# V4-POJ-STM32F103C8T6.net
KiCad netlist of a schematic drawn in EasyEDA Pro
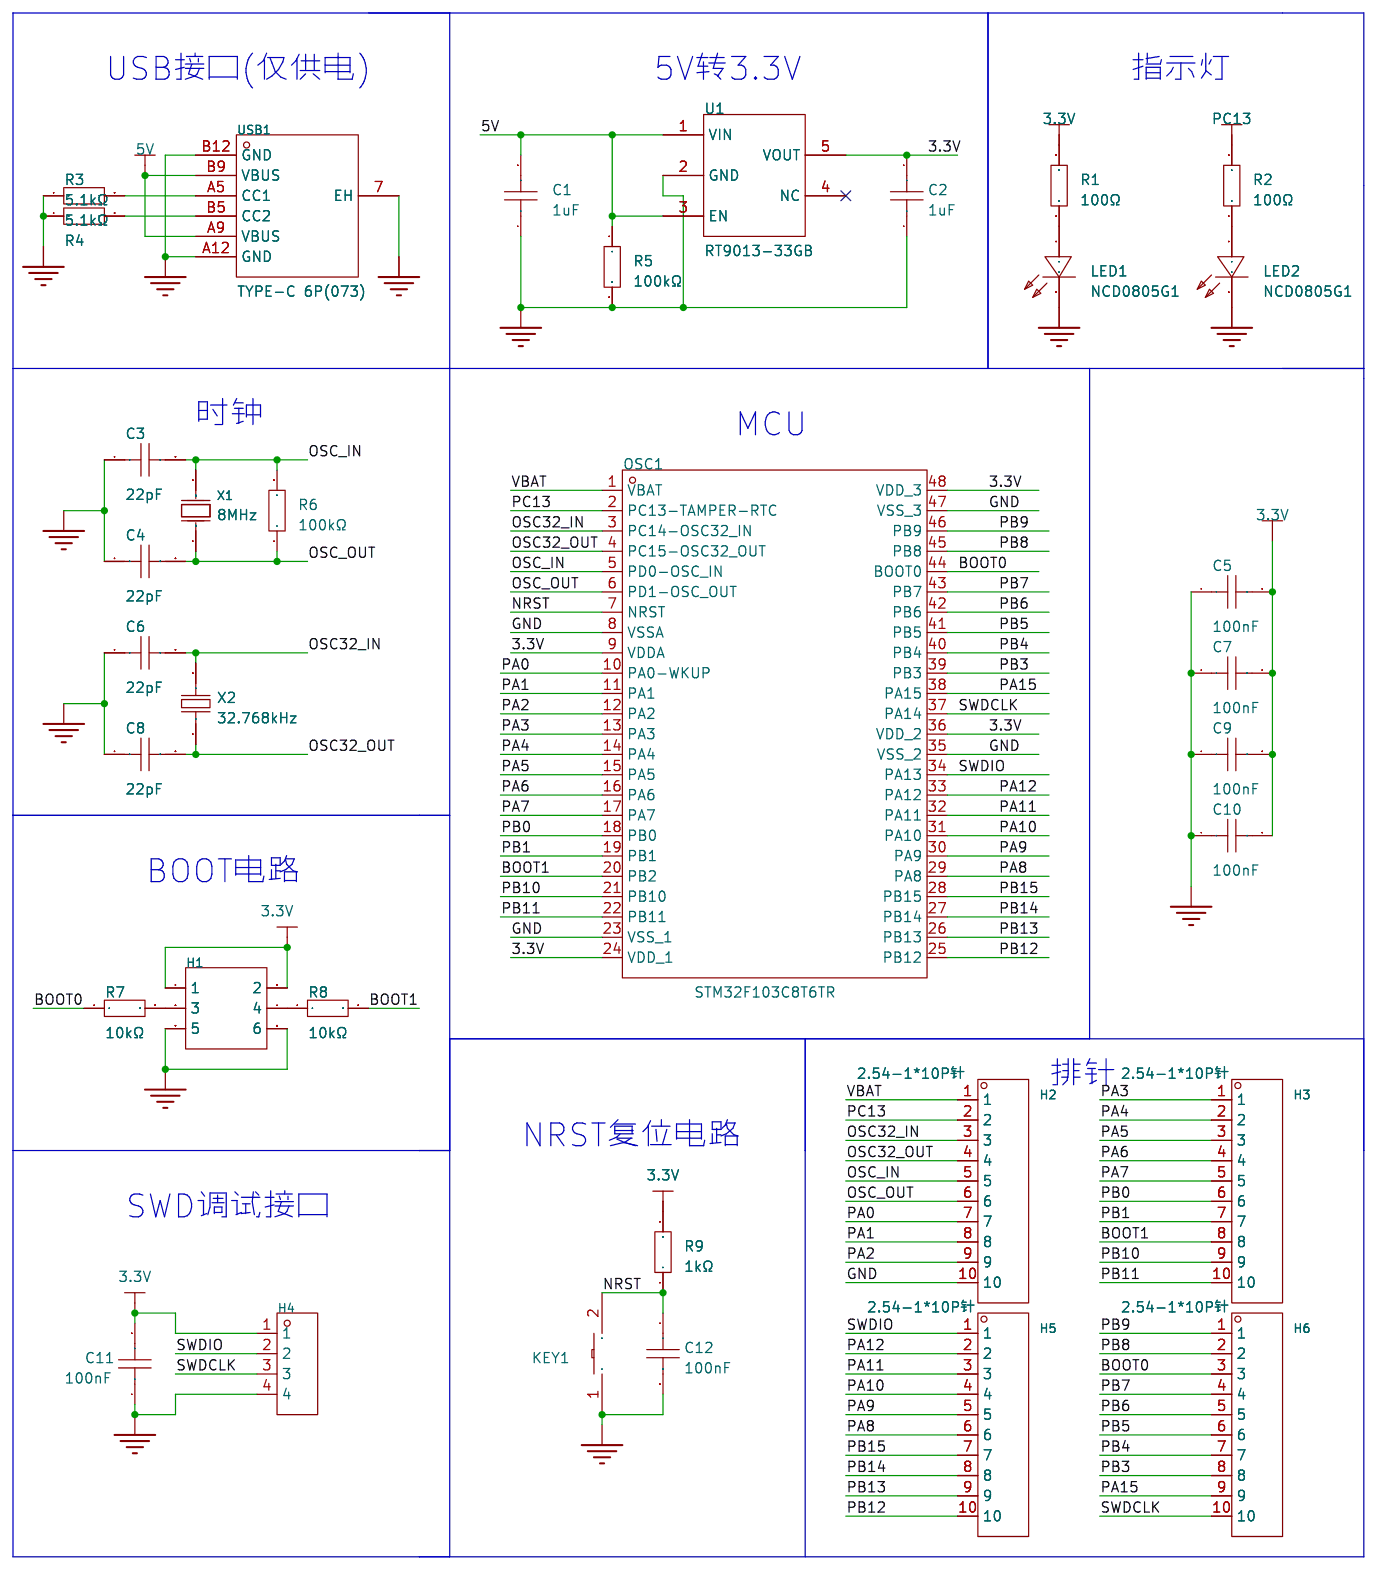
[diagram p0: schematic sheet]

(export (version "E")
  (design (tool "Eeschema 10.0.6"))
  (components
    (comp (ref "C1")
      (value "1uF")
      (footprint "easyedapro:C0603")
      (fields
        (field (name "Manufacturer Part") "CL21B105KBFNNNE")
        (field (name "Manufacturer") "SAMSUNG(三星)")
      )
      (libsource (lib "easyedapro") (part "CapAcitance"))
    )
    (comp (ref "C2")
      (value "1uF")
      (footprint "easyedapro:C0603")
      (fields
        (field (name "Manufacturer Part") "CL21B105KBFNNNE")
        (field (name "Manufacturer") "SAMSUNG(三星)")
      )
      (libsource (lib "easyedapro") (part "CapAcitance"))
    )
    (comp (ref "C3")
      (value "22pF")
      (footprint "easyedapro:C0805")
      (description "容值:22pF;精度:±5%;额定电压:50V;材质(温度系数):C0G;")
      (fields (field (name "Manufacturer Part") "0805CG220J500NT") (field (name "Manufacturer") "FH(风华)"))
      (libsource (lib "easyedapro") (part "0805CG220J500NT_C24658"))
    )
    (comp (ref "C4")
      (value "22pF")
      (footprint "easyedapro:C0805")
      (description "容值:22pF;精度:±5%;额定电压:50V;材质(温度系数):C0G;")
      (fields (field (name "Manufacturer Part") "0805CG220J500NT") (field (name "Manufacturer") "FH(风华)"))
      (libsource (lib "easyedapro") (part "0805CG220J500NT_C24658"))
    )
    (comp (ref "C5")
      (value "100nF")
      (footprint "easyedapro:C0603")
      (fields (field (name "Manufacturer Part") "0805B104K500NT") (field (name "Manufacturer") "FH(风华)"))
      (libsource (lib "easyedapro") (part "CapAcitance"))
    )
    (comp (ref "C6")
      (value "22pF")
      (footprint "easyedapro:C0805")
      (description "容值:22pF;精度:±5%;额定电压:50V;材质(温度系数):C0G;")
      (fields (field (name "Manufacturer Part") "0805CG220J500NT") (field (name "Manufacturer") "FH(风华)"))
      (libsource (lib "easyedapro") (part "0805CG220J500NT_C24658"))
    )
    (comp (ref "C7")
      (value "100nF")
      (footprint "easyedapro:C0603")
      (fields (field (name "Manufacturer Part") "0805B104K500NT") (field (name "Manufacturer") "FH(风华)"))
      (libsource (lib "easyedapro") (part "CapAcitance"))
    )
    (comp (ref "C8")
      (value "22pF")
      (footprint "easyedapro:C0805")
      (description "容值:22pF;精度:±5%;额定电压:50V;材质(温度系数):C0G;")
      (fields (field (name "Manufacturer Part") "0805CG220J500NT") (field (name "Manufacturer") "FH(风华)"))
      (libsource (lib "easyedapro") (part "0805CG220J500NT_C24658"))
    )
    (comp (ref "C9")
      (value "100nF")
      (footprint "easyedapro:C0603")
      (fields (field (name "Manufacturer Part") "0805B104K500NT") (field (name "Manufacturer") "FH(风华)"))
      (libsource (lib "easyedapro") (part "CapAcitance"))
    )
    (comp (ref "C10")
      (value "100nF")
      (footprint "easyedapro:C0603")
      (fields (field (name "Manufacturer Part") "0805B104K500NT") (field (name "Manufacturer") "FH(风华)"))
      (libsource (lib "easyedapro") (part "CapAcitance"))
    )
    (comp (ref "C11")
      (value "100nF")
      (footprint "easyedapro:C0603")
      (fields (field (name "Manufacturer Part") "0805B104K500NT") (field (name "Manufacturer") "FH(风华)"))
      (libsource (lib "easyedapro") (part "CapAcitance"))
    )
    (comp (ref "C12")
      (value "100nF")
      (footprint "easyedapro:C0603")
      (fields (field (name "Manufacturer Part") "0805B104K500NT") (field (name "Manufacturer") "FH(风华)"))
      (libsource (lib "easyedapro") (part "CapAcitance"))
    )
    (comp (ref "H1")
      (value "2.54-2*3P针")
      (footprint "easyedapro:HDR-TH_6P-P2.54-V-M-R2-C3-S2.54-1")
      (fields (field (name "Manufacturer") "BOOMELE(博穆精密)"))
      (libsource (lib "easyedapro") (part "Header-Male-2.54_2x3"))
    )
    (comp (ref "H2")
      (value "2.54-1*10P针")
      (footprint "easyedapro:HDR-TH_10P-P2.54-V-M-1")
      (fields (field (name "Manufacturer") "BOOMELE(博穆精密)"))
      (libsource (lib "easyedapro") (part "Header-Male-2.54_1x10"))
    )
    (comp (ref "H3")
      (value "2.54-1*10P针")
      (footprint "easyedapro:HDR-TH_10P-P2.54-V-M-1")
      (fields (field (name "Manufacturer") "BOOMELE(博穆精密)"))
      (libsource (lib "easyedapro") (part "Header-Male-2.54_1x10"))
    )
    (comp (ref "H4")
      (value "PZ254R-11-04P")
      (footprint "easyedapro:HDR-TH_4P-P2.54-V-M")
      (fields (field (name "Manufacturer") "XFCN(兴飞)"))
      (libsource (lib "easyedapro") (part "PZ254V-11-04P_C2691448"))
    )
    (comp (ref "H5")
      (value "2.54-1*10P针")
      (footprint "easyedapro:HDR-TH_10P-P2.54-V-M-1")
      (fields (field (name "Manufacturer") "BOOMELE(博穆精密)"))
      (libsource (lib "easyedapro") (part "Header-Male-2.54_1x10"))
    )
    (comp (ref "H6")
      (value "2.54-1*10P针")
      (footprint "easyedapro:HDR-TH_10P-P2.54-V-M-1")
      (fields (field (name "Manufacturer") "BOOMELE(博穆精密)"))
      (libsource (lib "easyedapro") (part "Header-Male-2.54_1x10"))
    )
    (comp (ref "KEY1")
      (value "TS-1101-C-W")
      (footprint "easyedapro:SW-SMD_L6.0-W3.3-LS8.0")
      (description "触点电流:50mA;额定电压(AC):-;额定电压(DC):12V;额定功率:-;绝缘电阻:-;电路结构:单刀单掷;安装方式:立贴;带灯:无;作用力:260gf;机械寿命:5万次;带支架:否;")
      (fields (field (name "Manufacturer") "XKB Connectivity(中国星坤)"))
      (libsource (lib "easyedapro") (part "TS-1101-C-W"))
    )
    (comp (ref "LED1")
      (value "NCD0805G1")
      (footprint "easyedapro:LED0805-R-RD")
      (description "发光颜色:翠绿;")
      (fields (field (name "Manufacturer") "国星光电"))
      (libsource (lib "easyedapro") (part "FC-2012UGK-520D5"))
    )
    (comp (ref "LED2")
      (value "NCD0805G1")
      (footprint "easyedapro:LED0805-R-RD")
      (description "发光颜色:翠绿;")
      (fields (field (name "Manufacturer") "国星光电"))
      (libsource (lib "easyedapro") (part "FC-2012UGK-520D5"))
    )
    (comp (ref "OSC1")
      (value "STM32F103C8T6TR")
      (footprint "easyedapro:LQFP-48_L7.0-W7.0-P0.50-LS9.0-BL")
      (fields (field (name "Manufacturer") "ST(意法半导体)"))
      (libsource (lib "easyedapro") (part "STM32F103C8T6TR"))
    )
    (comp (ref "R1")
      (value "100Ω")
      (footprint "easyedapro:R0603")
      (fields
        (field (name "Manufacturer Part") "0805W8F1000T5E")
        (field (name "Manufacturer") "UNI-ROYAL(厚声)")
      )
      (libsource (lib "easyedapro") (part "电阻"))
    )
    (comp (ref "R2")
      (value "100Ω")
      (footprint "easyedapro:R0603")
      (fields
        (field (name "Manufacturer Part") "0805W8F1000T5E")
        (field (name "Manufacturer") "UNI-ROYAL(厚声)")
      )
      (libsource (lib "easyedapro") (part "电阻"))
    )
    (comp (ref "R3")
      (value "5.1kΩ")
      (fields
        (field (name "Manufacturer Part") "0805W8F5101T5E")
        (field (name "Manufacturer") "UNI-ROYAL(厚声)")
      )
      (libsource (lib "easyedapro") (part "电阻"))
    )
    (comp (ref "R4")
      (value "5.1kΩ")
      (fields
        (field (name "Manufacturer Part") "0805W8F5101T5E")
        (field (name "Manufacturer") "UNI-ROYAL(厚声)")
      )
      (libsource (lib "easyedapro") (part "电阻"))
    )
    (comp (ref "R5")
      (value "100kΩ")
      (footprint "easyedapro:R0603")
      (description "阻值:100kΩ;精度:±1%;功率:125mW;温度系数:±100ppm/℃;电阻类型:厚膜电阻;")
      (fields
        (field (name "Manufacturer Part") "0805W8F1003T5E")
        (field (name "Manufacturer") "UNI-ROYAL(厚声)")
      )
      (libsource (lib "easyedapro") (part "电阻"))
    )
    (comp (ref "R6")
      (value "100kΩ")
      (footprint "easyedapro:R0805")
      (description "阻值:100kΩ;精度:±1%;功率:125mW;温度系数:±100ppm/℃;电阻类型:厚膜电阻;")
      (fields
        (field (name "Manufacturer Part") "0805W8F1003T5E")
        (field (name "Manufacturer") "UNI-ROYAL(厚声)")
      )
      (libsource (lib "easyedapro") (part "0805W8F1002T5E"))
    )
    (comp (ref "R7")
      (value "10kΩ")
      (footprint "easyedapro:R0603")
      (fields
        (field (name "Manufacturer Part") "0805W8F1002T5E")
        (field (name "Manufacturer") "UNI-ROYAL(厚声)")
      )
      (libsource (lib "easyedapro") (part "电阻"))
    )
    (comp (ref "R8")
      (value "10kΩ")
      (footprint "easyedapro:R0603")
      (fields
        (field (name "Manufacturer Part") "0805W8F1002T5E")
        (field (name "Manufacturer") "UNI-ROYAL(厚声)")
      )
      (libsource (lib "easyedapro") (part "电阻"))
    )
    (comp (ref "R9")
      (value "1kΩ")
      (footprint "easyedapro:R0603")
      (fields
        (field (name "Manufacturer Part") "0805W8F1001T5E")
        (field (name "Manufacturer") "UNI-ROYAL(厚声)")
      )
      (libsource (lib "easyedapro") (part "电阻"))
    )
    (comp (ref "U1")
      (value "RT9013-33GB")
      (footprint "easyedapro:SOT-23-5_L3.0-W1.7-P0.95-LS2.8-BL")
      (description "输出类型:固定;输出极性:正;最大输入电压:5.5V;输出电压:3.3V;输出电流:500mA;电源纹波抑制比(PSRR):50dB@(10kHz);")
      (fields (field (name "Manufacturer") "RICHTEK(立锜)"))
      (libsource (lib "easyedapro") (part "RT9013-33GB"))
    )
    (comp (ref "USB1")
      (value "TYPE-C 6P(073)")
      (footprint "easyedapro:TYPE-C-SMD_TYPE-C-6P")
      (description "连接器类型:Type-C;标准:-;公母:母座;触点数量:6P;端口数量:1;安装方式:卧贴;额定电流 - 电源:5A;工作温度范围:-25°C~+85°C;")
      (fields (field (name "Manufacturer") "SHOU HAN(首韩)"))
      (libsource (lib "easyedapro") (part "TYPE-C 6P(073)"))
    )
    (comp (ref "X1")
      (value "8MHz")
      (footprint "easyedapro:CRYSTAL-SMD_L5.0-W3.2")
      (description "频率:8MHz;负载电容:20pF;频率公差:±10ppm;")
      (fields (field (name "Manufacturer Part") "X50328MSB2GI") (field (name "Manufacturer") "YXC(扬兴晶振)"))
      (libsource (lib "easyedapro") (part "X50328MSB2GI"))
    )
    (comp (ref "X2")
      (value "32.768kHz")
      (footprint "easyedapro:FC-135R_L3.2-W1.5")
      (description "频率:32.768kHz;频率公差:±20ppm;负载电容:12.5pF;")
      (fields (field (name "Manufacturer Part") "Q13FC1350000400") (field (name "Manufacturer") "EPSON(爱普生)"))
      (libsource (lib "easyedapro") (part "Q13FC1350000400"))
    )
  )
  (nets
    (net (code "1") (name "/BOOT0") (class "Default")
      (node (ref "H6") (pin "3") (pinfunction "3_3") (pintype "input"))
      (node (ref "OSC1") (pin "44") (pinfunction "BOOT0_44") (pintype "input"))
      (node (ref "R7") (pin "1") (pinfunction "1_1") (pintype "input"))
    )
    (net (code "2") (name "/BOOT1") (class "Default")
      (node (ref "H3") (pin "8") (pinfunction "8_8") (pintype "input"))
      (node (ref "OSC1") (pin "20") (pinfunction "PB2_20") (pintype "input"))
      (node (ref "R8") (pin "2") (pinfunction "2_2") (pintype "input"))
    )
    (net (code "3") (name "/NRST") (class "Default")
      (node (ref "C12") (pin "1") (pinfunction "1_1") (pintype "input"))
      (node (ref "KEY1") (pin "2") (pinfunction "2_2") (pintype "input"))
      (node (ref "OSC1") (pin "7") (pinfunction "NRST_7") (pintype "input"))
      (node (ref "R9") (pin "1") (pinfunction "1_1") (pintype "input"))
    )
    (net (code "4") (name "/OSC32_IN") (class "Default")
      (node (ref "C6") (pin "2") (pinfunction "2_2") (pintype "input"))
      (node (ref "H2") (pin "3") (pinfunction "3_3") (pintype "input"))
      (node (ref "OSC1") (pin "3") (pinfunction "PC14-OSC32_IN_3") (pintype "input"))
      (node (ref "X2") (pin "2") (pinfunction "2_2") (pintype "input"))
    )
    (net (code "5") (name "/OSC32_OUT") (class "Default")
      (node (ref "C8") (pin "2") (pinfunction "2_2") (pintype "input"))
      (node (ref "H2") (pin "4") (pinfunction "4_4") (pintype "input"))
      (node (ref "OSC1") (pin "4") (pinfunction "PC15-OSC32_OUT_4") (pintype "input"))
      (node (ref "X2") (pin "1") (pinfunction "1_1") (pintype "input"))
    )
    (net (code "6") (name "/OSC_IN") (class "Default")
      (node (ref "C3") (pin "2") (pinfunction "2_2") (pintype "input"))
      (node (ref "H2") (pin "5") (pinfunction "5_5") (pintype "input"))
      (node (ref "OSC1") (pin "5") (pinfunction "PD0-OSC_IN_5") (pintype "input"))
      (node (ref "R6") (pin "2") (pinfunction "2_2") (pintype "input"))
      (node (ref "X1") (pin "2") (pinfunction "OSC2_2") (pintype "input"))
    )
    (net (code "7") (name "/OSC_OUT") (class "Default")
      (node (ref "C4") (pin "2") (pinfunction "2_2") (pintype "input"))
      (node (ref "H2") (pin "6") (pinfunction "6_6") (pintype "input"))
      (node (ref "OSC1") (pin "6") (pinfunction "PD1-OSC_OUT_6") (pintype "input"))
      (node (ref "R6") (pin "1") (pinfunction "1_1") (pintype "input"))
      (node (ref "X1") (pin "1") (pinfunction "OSC1_1") (pintype "input"))
    )
    (net (code "8") (name "/PA0") (class "Default")
      (node (ref "H2") (pin "7") (pinfunction "7_7") (pintype "input"))
      (node (ref "OSC1") (pin "10") (pinfunction "PA0-WKUP_10") (pintype "input"))
    )
    (net (code "9") (name "/PA1") (class "Default")
      (node (ref "H2") (pin "8") (pinfunction "8_8") (pintype "input"))
      (node (ref "OSC1") (pin "11") (pinfunction "PA1_11") (pintype "input"))
    )
    (net (code "10") (name "/PA2") (class "Default")
      (node (ref "H2") (pin "9") (pinfunction "9_9") (pintype "input"))
      (node (ref "OSC1") (pin "12") (pinfunction "PA2_12") (pintype "input"))
    )
    (net (code "11") (name "/PA3") (class "Default")
      (node (ref "H3") (pin "1") (pinfunction "1_1") (pintype "input"))
      (node (ref "OSC1") (pin "13") (pinfunction "PA3_13") (pintype "input"))
    )
    (net (code "12") (name "/PA4") (class "Default")
      (node (ref "H3") (pin "2") (pinfunction "2_2") (pintype "input"))
      (node (ref "OSC1") (pin "14") (pinfunction "PA4_14") (pintype "input"))
    )
    (net (code "13") (name "/PA5") (class "Default")
      (node (ref "H3") (pin "3") (pinfunction "3_3") (pintype "input"))
      (node (ref "OSC1") (pin "15") (pinfunction "PA5_15") (pintype "input"))
    )
    (net (code "14") (name "/PA6") (class "Default")
      (node (ref "H3") (pin "4") (pinfunction "4_4") (pintype "input"))
      (node (ref "OSC1") (pin "16") (pinfunction "PA6_16") (pintype "input"))
    )
    (net (code "15") (name "/PA7") (class "Default")
      (node (ref "H3") (pin "5") (pinfunction "5_5") (pintype "input"))
      (node (ref "OSC1") (pin "17") (pinfunction "PA7_17") (pintype "input"))
    )
    (net (code "16") (name "/PA8") (class "Default")
      (node (ref "H5") (pin "6") (pinfunction "6_6") (pintype "input"))
      (node (ref "OSC1") (pin "29") (pinfunction "PA8_29") (pintype "input"))
    )
    (net (code "17") (name "/PA9") (class "Default")
      (node (ref "H5") (pin "5") (pinfunction "5_5") (pintype "input"))
      (node (ref "OSC1") (pin "30") (pinfunction "PA9_30") (pintype "input"))
    )
    (net (code "18") (name "/PA10") (class "Default")
      (node (ref "H5") (pin "4") (pinfunction "4_4") (pintype "input"))
      (node (ref "OSC1") (pin "31") (pinfunction "PA10_31") (pintype "input"))
    )
    (net (code "19") (name "/PA11") (class "Default")
      (node (ref "H5") (pin "3") (pinfunction "3_3") (pintype "input"))
      (node (ref "OSC1") (pin "32") (pinfunction "PA11_32") (pintype "input"))
    )
    (net (code "20") (name "/PA12") (class "Default")
      (node (ref "H5") (pin "2") (pinfunction "2_2") (pintype "input"))
      (node (ref "OSC1") (pin "33") (pinfunction "PA12_33") (pintype "input"))
    )
    (net (code "21") (name "/PA15") (class "Default")
      (node (ref "H6") (pin "9") (pinfunction "9_9") (pintype "input"))
      (node (ref "OSC1") (pin "38") (pinfunction "PA15_38") (pintype "input"))
    )
    (net (code "22") (name "/PB0") (class "Default")
      (node (ref "H3") (pin "6") (pinfunction "6_6") (pintype "input"))
      (node (ref "OSC1") (pin "18") (pinfunction "PB0_18") (pintype "input"))
    )
    (net (code "23") (name "/PB1") (class "Default")
      (node (ref "H3") (pin "7") (pinfunction "7_7") (pintype "input"))
      (node (ref "OSC1") (pin "19") (pinfunction "PB1_19") (pintype "input"))
    )
    (net (code "24") (name "/PB3") (class "Default")
      (node (ref "H6") (pin "8") (pinfunction "8_8") (pintype "input"))
      (node (ref "OSC1") (pin "39") (pinfunction "PB3_39") (pintype "input"))
    )
    (net (code "25") (name "/PB4") (class "Default")
      (node (ref "H6") (pin "7") (pinfunction "7_7") (pintype "input"))
      (node (ref "OSC1") (pin "40") (pinfunction "PB4_40") (pintype "input"))
    )
    (net (code "26") (name "/PB5") (class "Default")
      (node (ref "H6") (pin "6") (pinfunction "6_6") (pintype "input"))
      (node (ref "OSC1") (pin "41") (pinfunction "PB5_41") (pintype "input"))
    )
    (net (code "27") (name "/PB6") (class "Default")
      (node (ref "H6") (pin "5") (pinfunction "5_5") (pintype "input"))
      (node (ref "OSC1") (pin "42") (pinfunction "PB6_42") (pintype "input"))
    )
    (net (code "28") (name "/PB7") (class "Default")
      (node (ref "H6") (pin "4") (pinfunction "4_4") (pintype "input"))
      (node (ref "OSC1") (pin "43") (pinfunction "PB7_43") (pintype "input"))
    )
    (net (code "29") (name "/PB8") (class "Default")
      (node (ref "H6") (pin "2") (pinfunction "2_2") (pintype "input"))
      (node (ref "OSC1") (pin "45") (pinfunction "PB8_45") (pintype "input"))
    )
    (net (code "30") (name "/PB9") (class "Default")
      (node (ref "H6") (pin "1") (pinfunction "1_1") (pintype "input"))
      (node (ref "OSC1") (pin "46") (pinfunction "PB9_46") (pintype "input"))
    )
    (net (code "31") (name "/PB10") (class "Default")
      (node (ref "H3") (pin "9") (pinfunction "9_9") (pintype "input"))
      (node (ref "OSC1") (pin "21") (pinfunction "PB10_21") (pintype "input"))
    )
    (net (code "32") (name "/PB11") (class "Default")
      (node (ref "H3") (pin "10") (pinfunction "10_10") (pintype "input"))
      (node (ref "OSC1") (pin "22") (pinfunction "PB11_22") (pintype "input"))
    )
    (net (code "33") (name "/PB12") (class "Default")
      (node (ref "H5") (pin "10") (pinfunction "10_10") (pintype "input"))
      (node (ref "OSC1") (pin "25") (pinfunction "PB12_25") (pintype "input"))
    )
    (net (code "34") (name "/PB13") (class "Default")
      (node (ref "H5") (pin "9") (pinfunction "9_9") (pintype "input"))
      (node (ref "OSC1") (pin "26") (pinfunction "PB13_26") (pintype "input"))
    )
    (net (code "35") (name "/PB14") (class "Default")
      (node (ref "H5") (pin "8") (pinfunction "8_8") (pintype "input"))
      (node (ref "OSC1") (pin "27") (pinfunction "PB14_27") (pintype "input"))
    )
    (net (code "36") (name "/PB15") (class "Default")
      (node (ref "H5") (pin "7") (pinfunction "7_7") (pintype "input"))
      (node (ref "OSC1") (pin "28") (pinfunction "PB15_28") (pintype "input"))
    )
    (net (code "37") (name "/SWDCLK") (class "Default")
      (node (ref "H4") (pin "3") (pinfunction "3_3") (pintype "input"))
      (node (ref "H6") (pin "10") (pinfunction "10_10") (pintype "input"))
      (node (ref "OSC1") (pin "37") (pinfunction "PA14_37") (pintype "input"))
    )
    (net (code "38") (name "/SWDIO") (class "Default")
      (node (ref "H4") (pin "2") (pinfunction "2_2") (pintype "input"))
      (node (ref "H5") (pin "1") (pinfunction "1_1") (pintype "input"))
      (node (ref "OSC1") (pin "34") (pinfunction "PA13_34") (pintype "input"))
    )
    (net (code "39") (name "/VBAT") (class "Default")
      (node (ref "H2") (pin "1") (pinfunction "1_1") (pintype "input"))
      (node (ref "OSC1") (pin "1") (pinfunction "VBAT_1") (pintype "input"))
    )
    (net (code "40") (name "3.3V") (class "Default")
      (node (ref "C10") (pin "2") (pinfunction "2_2") (pintype "input"))
      (node (ref "C11") (pin "2") (pinfunction "2_2") (pintype "input"))
      (node (ref "C2") (pin "2") (pinfunction "2_2") (pintype "input"))
      (node (ref "C5") (pin "2") (pinfunction "2_2") (pintype "input"))
      (node (ref "C7") (pin "2") (pinfunction "2_2") (pintype "input"))
      (node (ref "C9") (pin "2") (pinfunction "2_2") (pintype "input"))
      (node (ref "H1") (pin "1") (pinfunction "1_1") (pintype "input"))
      (node (ref "H1") (pin "2") (pinfunction "2_2") (pintype "input"))
      (node (ref "H4") (pin "1") (pinfunction "1_1") (pintype "input"))
      (node (ref "OSC1") (pin "24") (pinfunction "VDD_1_24") (pintype "input"))
      (node (ref "OSC1") (pin "36") (pinfunction "VDD_2_36") (pintype "input"))
      (node (ref "OSC1") (pin "48") (pinfunction "VDD_3_48") (pintype "input"))
      (node (ref "OSC1") (pin "9") (pinfunction "VDDA_9") (pintype "input"))
      (node (ref "R1") (pin "2") (pinfunction "2_2") (pintype "input"))
      (node (ref "R9") (pin "2") (pinfunction "2_2") (pintype "input"))
      (node (ref "U1") (pin "5") (pinfunction "VOUT_5") (pintype "unspecified"))
    )
    (net (code "41") (name "5V") (class "Default")
      (node (ref "C1") (pin "2") (pinfunction "2_2") (pintype "input"))
      (node (ref "R5") (pin "1") (pinfunction "1_1") (pintype "input"))
      (node (ref "U1") (pin "1") (pinfunction "VIN_1") (pintype "unspecified"))
      (node (ref "U1") (pin "3") (pinfunction "EN_3") (pintype "unspecified"))
      (node (ref "USB1") (pin "A9") (pinfunction "VBUS_A9") (pintype "input"))
      (node (ref "USB1") (pin "B9") (pinfunction "VBUS_B9") (pintype "input"))
    )
    (net (code "42") (name "GND") (class "Default")
      (node (ref "C1") (pin "1") (pinfunction "1_1") (pintype "input"))
      (node (ref "C10") (pin "1") (pinfunction "1_1") (pintype "input"))
      (node (ref "C11") (pin "1") (pinfunction "1_1") (pintype "input"))
      (node (ref "C12") (pin "2") (pinfunction "2_2") (pintype "input"))
      (node (ref "C2") (pin "1") (pinfunction "1_1") (pintype "input"))
      (node (ref "C3") (pin "1") (pinfunction "1_1") (pintype "input"))
      (node (ref "C4") (pin "1") (pinfunction "1_1") (pintype "input"))
      (node (ref "C5") (pin "1") (pinfunction "1_1") (pintype "input"))
      (node (ref "C6") (pin "1") (pinfunction "1_1") (pintype "input"))
      (node (ref "C7") (pin "1") (pinfunction "1_1") (pintype "input"))
      (node (ref "C8") (pin "1") (pinfunction "1_1") (pintype "input"))
      (node (ref "C9") (pin "1") (pinfunction "1_1") (pintype "input"))
      (node (ref "H1") (pin "5") (pinfunction "5_5") (pintype "input"))
      (node (ref "H1") (pin "6") (pinfunction "6_6") (pintype "input"))
      (node (ref "H2") (pin "10") (pinfunction "10_10") (pintype "input"))
      (node (ref "H4") (pin "4") (pinfunction "4_4") (pintype "input"))
      (node (ref "KEY1") (pin "1") (pinfunction "1_1") (pintype "input"))
      (node (ref "LED1") (pin "2") (pinfunction "K_2") (pintype "unspecified"))
      (node (ref "LED2") (pin "2") (pinfunction "K_2") (pintype "unspecified"))
      (node (ref "OSC1") (pin "23") (pinfunction "VSS_1_23") (pintype "input"))
      (node (ref "OSC1") (pin "35") (pinfunction "VSS_2_35") (pintype "input"))
      (node (ref "OSC1") (pin "47") (pinfunction "VSS_3_47") (pintype "input"))
      (node (ref "OSC1") (pin "8") (pinfunction "VSSA_8") (pintype "input"))
      (node (ref "R3") (pin "1") (pinfunction "1_1") (pintype "input"))
      (node (ref "R4") (pin "1") (pinfunction "1_1") (pintype "input"))
      (node (ref "R5") (pin "2") (pinfunction "2_2") (pintype "input"))
      (node (ref "U1") (pin "2") (pinfunction "GND_2") (pintype "unspecified"))
      (node (ref "USB1") (pin "7") (pinfunction "EH_7") (pintype "input"))
      (node (ref "USB1") (pin "A12") (pinfunction "GND_A12") (pintype "input"))
      (node (ref "USB1") (pin "B12") (pinfunction "GND_B12") (pintype "input"))
    )
    (net (code "43") (name "Net-(H1-Pad3)") (class "Default")
      (node (ref "H1") (pin "3") (pinfunction "3_3") (pintype "input"))
      (node (ref "R7") (pin "2") (pinfunction "2_2") (pintype "input"))
    )
    (net (code "44") (name "Net-(H1-Pad4)") (class "Default")
      (node (ref "H1") (pin "4") (pinfunction "4_4") (pintype "input"))
      (node (ref "R8") (pin "1") (pinfunction "1_1") (pintype "input"))
    )
    (net (code "45") (name "Net-(LED1-A)") (class "Default")
      (node (ref "LED1") (pin "1") (pinfunction "A_1") (pintype "unspecified"))
      (node (ref "R1") (pin "1") (pinfunction "1_1") (pintype "input"))
    )
    (net (code "46") (name "Net-(LED2-A)") (class "Default")
      (node (ref "LED2") (pin "1") (pinfunction "A_1") (pintype "unspecified"))
      (node (ref "R2") (pin "1") (pinfunction "1_1") (pintype "input"))
    )
    (net (code "47") (name "Net-(USB1-CC1)") (class "Default")
      (node (ref "R3") (pin "2") (pinfunction "2_2") (pintype "input"))
      (node (ref "USB1") (pin "A5") (pinfunction "CC1_A5") (pintype "input"))
    )
    (net (code "48") (name "Net-(USB1-CC2)") (class "Default")
      (node (ref "R4") (pin "2") (pinfunction "2_2") (pintype "input"))
      (node (ref "USB1") (pin "B5") (pinfunction "CC2_B5") (pintype "input"))
    )
    (net (code "49") (name "PC13") (class "Default")
      (node (ref "H2") (pin "2") (pinfunction "2_2") (pintype "input"))
      (node (ref "OSC1") (pin "2") (pinfunction "PC13-TAMPER-RTC_2") (pintype "input"))
      (node (ref "R2") (pin "2") (pinfunction "2_2") (pintype "input"))
    )
    (net (code "50") (name "unconnected-(U1-NC-Pad4)") (class "Default")
      (node (ref "U1") (pin "4") (pinfunction "NC_4") (pintype "unspecified+no_connect"))
    )
  )
)
